# FirstStandaloneMega.net
KiCad netlist of a schematic drawn in EAGLE
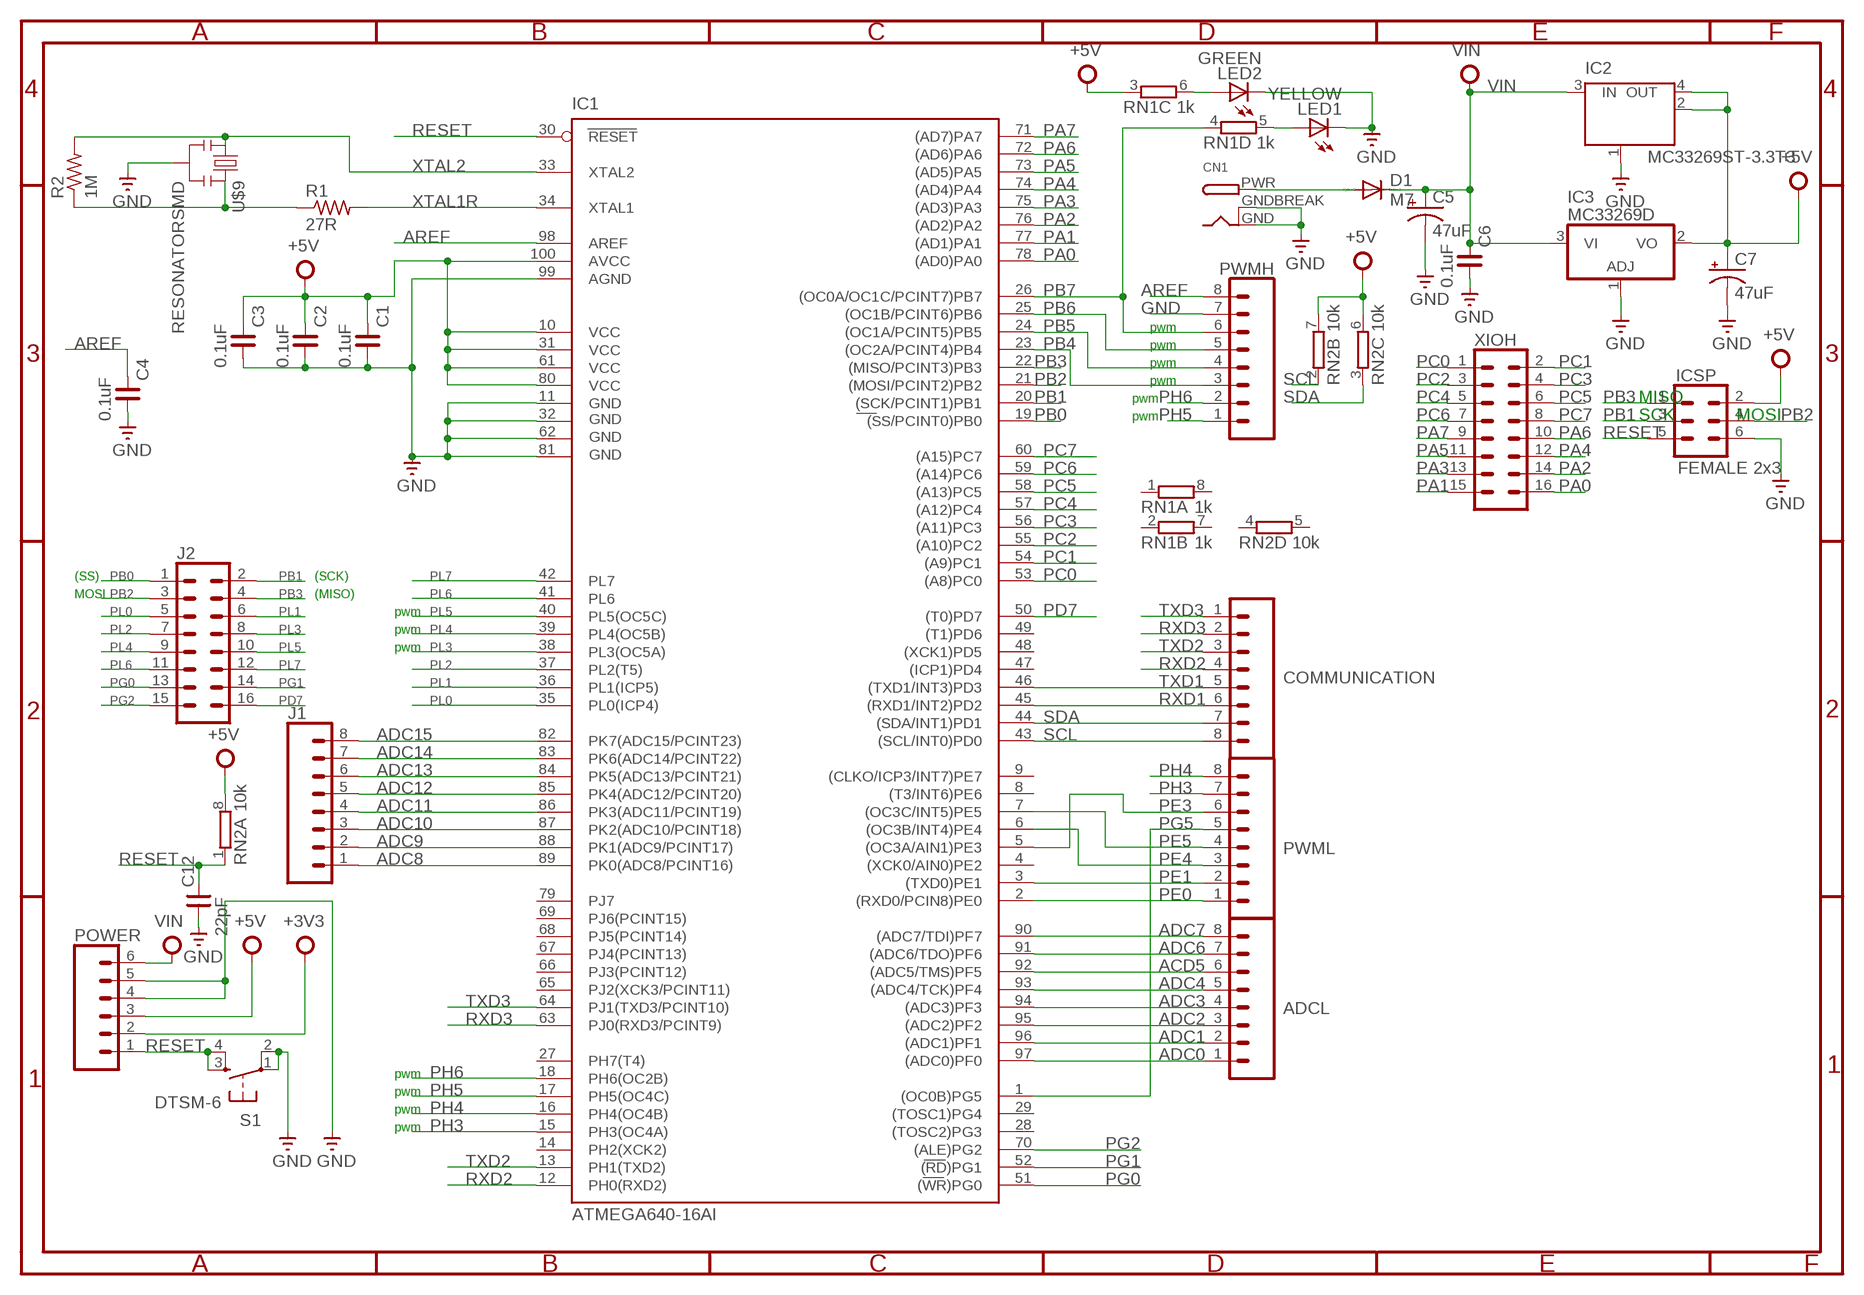
[diagram p0: schematic, sheet 1]

(export (version "E")
  (design (tool "Eeschema 10.0.6"))
  (components
    (comp (ref "ADCL")
      (value "CONN_08\"")
      (footprint "eagle-import:1X08")
      (libsource (lib "eagle-import") (part "CONN_08{dblquote}"))
    )
    (comp (ref "C1")
      (value "0.1uF")
      (footprint "eagle-import:C0805")
      (libsource (lib "eagle-import") (part "C_0805"))
    )
    (comp (ref "C2")
      (value "0.1uF")
      (footprint "eagle-import:C0805")
      (libsource (lib "eagle-import") (part "C_0805"))
    )
    (comp (ref "C3")
      (value "0.1uF")
      (footprint "eagle-import:C0805")
      (libsource (lib "eagle-import") (part "C_0805"))
    )
    (comp (ref "C4")
      (value "0.1uF")
      (footprint "eagle-import:C0805")
      (libsource (lib "eagle-import") (part "C_0805"))
    )
    (comp (ref "C5")
      (value "47uF")
      (footprint "eagle-import:PANASONIC_D")
      (libsource (lib "eagle-import") (part "CPOL-USD"))
    )
    (comp (ref "C6")
      (value "0.1uF")
      (footprint "eagle-import:C0805")
      (libsource (lib "eagle-import") (part "C_0805"))
    )
    (comp (ref "C7")
      (value "47uF")
      (footprint "eagle-import:PANASONIC_D")
      (libsource (lib "eagle-import") (part "CPOL-USD"))
    )
    (comp (ref "C12")
      (value "22pF")
      (footprint "eagle-import:0805")
      (libsource (lib "eagle-import") (part "CNP-0805"))
    )
    (comp (ref "CN1")
      (value "DCBARRELPTH")
      (footprint "eagle-import:DCJACK_2MM_PTH")
      (libsource (lib "eagle-import") (part "DCBARRELPTH"))
    )
    (comp (ref "COMMUNICATION")
      (value "CONN_08\"")
      (footprint "eagle-import:1X08")
      (libsource (lib "eagle-import") (part "CONN_08{dblquote}"))
    )
    (comp (ref "D1")
      (value "M7")
      (footprint "eagle-import:SMB")
      (libsource (lib "eagle-import") (part "DIODE-SMB"))
    )
    (comp (ref "IC1")
      (value "ATMEGA640-16AI")
      (footprint "eagle-import:TQFP100")
      (libsource (lib "eagle-import") (part "ATMEGAAI640-16"))
    )
    (comp (ref "IC2")
      (value "MC33269ST-3.3T3")
      (footprint "eagle-import:SOT223")
      (libsource (lib "eagle-import") (part "MC33269ST-3.3T3"))
    )
    (comp (ref "IC3")
      (value "MC33269D")
      (footprint "eagle-import:DPACK")
      (libsource (lib "eagle-import") (part "MC33269?D"))
    )
    (comp (ref "ICSP")
      (value "FEMALE 2x3")
      (footprint "eagle-import:2X3")
      (libsource (lib "eagle-import") (part "CONN_03X2FEMALE"))
    )
    (comp (ref "J1")
      (value "CONN_08\"")
      (footprint "eagle-import:1X08")
      (libsource (lib "eagle-import") (part "CONN_08{dblquote}"))
    )
    (comp (ref "J2")
      (value "CONN_08X2")
      (footprint "eagle-import:2X8")
      (libsource (lib "eagle-import") (part "CONN_08X2"))
    )
    (comp (ref "LED1")
      (value "YELLOW")
      (footprint "eagle-import:CHIPLED_0805")
      (libsource (lib "eagle-import") (part "LEDCHIPLED_0805"))
    )
    (comp (ref "LED2")
      (value "GREEN")
      (footprint "eagle-import:CHIPLED_0805")
      (libsource (lib "eagle-import") (part "LEDCHIPLED_0805"))
    )
    (comp (ref "POWER")
      (value "CONN_06SILK_FEMALE_PTH")
      (footprint "eagle-import:1X06")
      (libsource (lib "eagle-import") (part "CONN_06SILK_FEMALE_PTH"))
    )
    (comp (ref "PWMH")
      (value "CONN_08\"")
      (footprint "eagle-import:1X08")
      (libsource (lib "eagle-import") (part "CONN_08{dblquote}"))
    )
    (comp (ref "PWML")
      (value "CONN_08\"")
      (footprint "eagle-import:1X08")
      (libsource (lib "eagle-import") (part "CONN_08{dblquote}"))
    )
    (comp (ref "R1")
      (value "27R")
      (footprint "eagle-import:R0805")
      (libsource (lib "eagle-import") (part "R-US_R0805"))
    )
    (comp (ref "R2")
      (value "1M")
      (footprint "eagle-import:R0805")
      (libsource (lib "eagle-import") (part "R-US_R0805"))
    )
    (comp (ref "RN1")
      (value "1k")
      (footprint "eagle-import:CAY16")
      (libsource (lib "eagle-import") (part "4R-NCAY16"))
    )
    (comp (ref "RN2")
      (value "10k")
      (footprint "eagle-import:CAY16")
      (libsource (lib "eagle-import") (part "4R-NCAY16"))
    )
    (comp (ref "S1")
      (value "DTSM-6")
      (footprint "eagle-import:DTSM-6")
      (libsource (lib "eagle-import") (part "DTSM-6"))
    )
    (comp (ref "U$9")
      (value "RESONATORSMD")
      (footprint "eagle-import:RESONATOR-SMD")
      (libsource (lib "eagle-import") (part "RESONATORSMD"))
    )
    (comp (ref "XIOH")
      (value "CONN_08X2")
      (footprint "eagle-import:2X8")
      (libsource (lib "eagle-import") (part "CONN_08X2"))
    )
  )
  (nets
    (net (code "1") (name "+3V3") (class "Default")
      (node (ref "POWER") (pin "2") (pinfunction "2_2") (pintype "passive"))
    )
    (net (code "2") (name "+5V") (class "Default")
      (node (ref "C1") (pin "2") (pinfunction "2_2") (pintype "passive"))
      (node (ref "C2") (pin "2") (pinfunction "2_2") (pintype "passive"))
      (node (ref "C3") (pin "2") (pinfunction "2_2") (pintype "passive"))
      (node (ref "C7") (pin "+") (pinfunction "+_+") (pintype "passive"))
      (node (ref "IC1") (pin "10") (pinfunction "VCC_10") (pintype "power_in"))
      (node (ref "IC1") (pin "100") (pinfunction "AVCC_100") (pintype "power_in"))
      (node (ref "IC1") (pin "31") (pinfunction "VCC1_31") (pintype "power_in"))
      (node (ref "IC1") (pin "61") (pinfunction "VCC2_61") (pintype "power_in"))
      (node (ref "IC1") (pin "80") (pinfunction "VCC3_80") (pintype "power_in"))
      (node (ref "IC2") (pin "2") (pinfunction "OUT_2") (pintype "passive"))
      (node (ref "IC2") (pin "4") (pinfunction "OUT_4") (pintype "passive"))
      (node (ref "IC3") (pin "2") (pinfunction "VO_2") (pintype "passive"))
      (node (ref "ICSP") (pin "2") (pinfunction "2_2") (pintype "bidirectional"))
      (node (ref "POWER") (pin "3") (pinfunction "3_3") (pintype "passive"))
      (node (ref "RN1") (pin "3") (pinfunction "1_3") (pintype "passive"))
      (node (ref "RN2") (pin "6") (pinfunction "2_6") (pintype "passive"))
      (node (ref "RN2") (pin "7") (pinfunction "2_7") (pintype "passive"))
      (node (ref "RN2") (pin "8") (pinfunction "2_8") (pintype "passive"))
    )
    (net (code "3") (name "/ACD5") (class "Default")
      (node (ref "ADCL") (pin "6") (pinfunction "6_6") (pintype "passive"))
      (node (ref "IC1") (pin "92") (pinfunction "(ADC5/TMS)PF5_92") (pintype "bidirectional"))
    )
    (net (code "4") (name "/ADC0") (class "Default")
      (node (ref "ADCL") (pin "1") (pinfunction "1_1") (pintype "passive"))
      (node (ref "IC1") (pin "97") (pinfunction "(ADC0)PF0_97") (pintype "bidirectional"))
    )
    (net (code "5") (name "/ADC1") (class "Default")
      (node (ref "ADCL") (pin "2") (pinfunction "2_2") (pintype "passive"))
      (node (ref "IC1") (pin "96") (pinfunction "(ADC1)PF1_96") (pintype "bidirectional"))
    )
    (net (code "6") (name "/ADC2") (class "Default")
      (node (ref "ADCL") (pin "3") (pinfunction "3_3") (pintype "passive"))
      (node (ref "IC1") (pin "95") (pinfunction "(ADC2)PF2_95") (pintype "bidirectional"))
    )
    (net (code "7") (name "/ADC3") (class "Default")
      (node (ref "ADCL") (pin "4") (pinfunction "4_4") (pintype "passive"))
      (node (ref "IC1") (pin "94") (pinfunction "(ADC3)PF3_94") (pintype "bidirectional"))
    )
    (net (code "8") (name "/ADC4") (class "Default")
      (node (ref "ADCL") (pin "5") (pinfunction "5_5") (pintype "passive"))
      (node (ref "IC1") (pin "93") (pinfunction "(ADC4/TCK)PF4_93") (pintype "bidirectional"))
    )
    (net (code "9") (name "/ADC6") (class "Default")
      (node (ref "ADCL") (pin "7") (pinfunction "7_7") (pintype "passive"))
      (node (ref "IC1") (pin "91") (pinfunction "(ADC6/TDO)PF6_91") (pintype "bidirectional"))
    )
    (net (code "10") (name "/ADC7") (class "Default")
      (node (ref "ADCL") (pin "8") (pinfunction "8_8") (pintype "passive"))
      (node (ref "IC1") (pin "90") (pinfunction "(ADC7/TDI)PF7_90") (pintype "bidirectional"))
    )
    (net (code "11") (name "/ADC8") (class "Default")
      (node (ref "IC1") (pin "89") (pinfunction "PK0(ADC8/PCINT16)_89") (pintype "bidirectional"))
      (node (ref "J1") (pin "1") (pinfunction "1_1") (pintype "passive"))
    )
    (net (code "12") (name "/ADC9") (class "Default")
      (node (ref "IC1") (pin "88") (pinfunction "PK1(ADC9/PCINT17)_88") (pintype "bidirectional"))
      (node (ref "J1") (pin "2") (pinfunction "2_2") (pintype "passive"))
    )
    (net (code "13") (name "/ADC10") (class "Default")
      (node (ref "IC1") (pin "87") (pinfunction "PK2(ADC10/PCINT18)_87") (pintype "bidirectional"))
      (node (ref "J1") (pin "3") (pinfunction "3_3") (pintype "passive"))
    )
    (net (code "14") (name "/ADC11") (class "Default")
      (node (ref "IC1") (pin "86") (pinfunction "PK3(ADC11/PCINT19)_86") (pintype "bidirectional"))
      (node (ref "J1") (pin "4") (pinfunction "4_4") (pintype "passive"))
    )
    (net (code "15") (name "/ADC12") (class "Default")
      (node (ref "IC1") (pin "85") (pinfunction "PK4(ADC12/PCINT20)_85") (pintype "bidirectional"))
      (node (ref "J1") (pin "5") (pinfunction "5_5") (pintype "passive"))
    )
    (net (code "16") (name "/ADC13") (class "Default")
      (node (ref "IC1") (pin "84") (pinfunction "PK5(ADC13/PCINT21)_84") (pintype "bidirectional"))
      (node (ref "J1") (pin "6") (pinfunction "6_6") (pintype "passive"))
    )
    (net (code "17") (name "/ADC14") (class "Default")
      (node (ref "IC1") (pin "83") (pinfunction "PK6(ADC14/PCINT22)_83") (pintype "bidirectional"))
      (node (ref "J1") (pin "7") (pinfunction "7_7") (pintype "passive"))
    )
    (net (code "18") (name "/ADC15") (class "Default")
      (node (ref "IC1") (pin "82") (pinfunction "PK7(ADC15/PCINT23)_82") (pintype "bidirectional"))
      (node (ref "J1") (pin "8") (pinfunction "8_8") (pintype "passive"))
    )
    (net (code "19") (name "/AREF") (class "Default")
      (node (ref "C4") (pin "2") (pinfunction "2_2") (pintype "passive"))
      (node (ref "IC1") (pin "98") (pinfunction "AREF_98") (pintype "bidirectional"))
      (node (ref "PWMH") (pin "8") (pinfunction "8_8") (pintype "passive"))
    )
    (net (code "20") (name "/PA0") (class "Default")
      (node (ref "IC1") (pin "78") (pinfunction "(AD0)PA0_78") (pintype "bidirectional"))
      (node (ref "XIOH") (pin "16") (pinfunction "16_16") (pintype "passive"))
    )
    (net (code "21") (name "/PA1") (class "Default")
      (node (ref "IC1") (pin "77") (pinfunction "(AD1)PA1_77") (pintype "bidirectional"))
      (node (ref "XIOH") (pin "15") (pinfunction "15_15") (pintype "passive"))
    )
    (net (code "22") (name "/PA2") (class "Default")
      (node (ref "IC1") (pin "76") (pinfunction "(AD2)PA2_76") (pintype "bidirectional"))
      (node (ref "XIOH") (pin "14") (pinfunction "14_14") (pintype "passive"))
    )
    (net (code "23") (name "/PA3") (class "Default")
      (node (ref "IC1") (pin "75") (pinfunction "(AD3)PA3_75") (pintype "bidirectional"))
      (node (ref "XIOH") (pin "13") (pinfunction "13_13") (pintype "passive"))
    )
    (net (code "24") (name "/PA4") (class "Default")
      (node (ref "IC1") (pin "74") (pinfunction "(AD4)PA4_74") (pintype "bidirectional"))
      (node (ref "XIOH") (pin "12") (pinfunction "12_12") (pintype "passive"))
    )
    (net (code "25") (name "/PA5") (class "Default")
      (node (ref "IC1") (pin "73") (pinfunction "(AD5)PA5_73") (pintype "bidirectional"))
      (node (ref "XIOH") (pin "11") (pinfunction "11_11") (pintype "passive"))
    )
    (net (code "26") (name "/PA6") (class "Default")
      (node (ref "IC1") (pin "72") (pinfunction "(AD6)PA6_72") (pintype "bidirectional"))
      (node (ref "XIOH") (pin "10") (pinfunction "10_10") (pintype "passive"))
    )
    (net (code "27") (name "/PA7") (class "Default")
      (node (ref "IC1") (pin "71") (pinfunction "(AD7)PA7_71") (pintype "bidirectional"))
      (node (ref "XIOH") (pin "9") (pinfunction "9_9") (pintype "passive"))
    )
    (net (code "28") (name "/PB0") (class "Default")
      (node (ref "IC1") (pin "19") (pinfunction "(SS/PCINT0)PB0_19") (pintype "bidirectional"))
      (node (ref "J2") (pin "1") (pinfunction "1_1") (pintype "passive"))
    )
    (net (code "29") (name "/PB1") (class "Default")
      (node (ref "IC1") (pin "20") (pinfunction "(SCK/PCINT1)PB1_20") (pintype "bidirectional"))
      (node (ref "ICSP") (pin "3") (pinfunction "3_3") (pintype "bidirectional"))
      (node (ref "J2") (pin "2") (pinfunction "2_2") (pintype "passive"))
    )
    (net (code "30") (name "/PB2") (class "Default")
      (node (ref "IC1") (pin "21") (pinfunction "(MOSI/PCINT2)PB2_21") (pintype "bidirectional"))
      (node (ref "ICSP") (pin "4") (pinfunction "4_4") (pintype "bidirectional"))
      (node (ref "J2") (pin "3") (pinfunction "3_3") (pintype "passive"))
    )
    (net (code "31") (name "/PB3") (class "Default")
      (node (ref "IC1") (pin "22") (pinfunction "(MISO/PCINT3)PB3_22") (pintype "bidirectional"))
      (node (ref "ICSP") (pin "1") (pinfunction "1_1") (pintype "bidirectional"))
      (node (ref "J2") (pin "4") (pinfunction "4_4") (pintype "passive"))
    )
    (net (code "32") (name "/PB4") (class "Default")
      (node (ref "IC1") (pin "23") (pinfunction "(OC2A/PCINT4)PB4_23") (pintype "bidirectional"))
      (node (ref "PWMH") (pin "3") (pinfunction "3_3") (pintype "passive"))
    )
    (net (code "33") (name "/PB5") (class "Default")
      (node (ref "IC1") (pin "24") (pinfunction "(OC1A/PCINT5)PB5_24") (pintype "bidirectional"))
      (node (ref "PWMH") (pin "4") (pinfunction "4_4") (pintype "passive"))
    )
    (net (code "34") (name "/PB6") (class "Default")
      (node (ref "IC1") (pin "25") (pinfunction "(OC1B/PCINT6)PB6_25") (pintype "bidirectional"))
      (node (ref "PWMH") (pin "5") (pinfunction "5_5") (pintype "passive"))
    )
    (net (code "35") (name "/PB7") (class "Default")
      (node (ref "IC1") (pin "26") (pinfunction "(OC0A/OC1C/PCINT7)PB7_26") (pintype "bidirectional"))
      (node (ref "PWMH") (pin "6") (pinfunction "6_6") (pintype "passive"))
      (node (ref "RN1") (pin "4") (pinfunction "1_4") (pintype "passive"))
    )
    (net (code "36") (name "/PC0") (class "Default")
      (node (ref "IC1") (pin "53") (pinfunction "(A8)PC0_53") (pintype "bidirectional"))
      (node (ref "XIOH") (pin "1") (pinfunction "1_1") (pintype "passive"))
    )
    (net (code "37") (name "/PC1") (class "Default")
      (node (ref "IC1") (pin "54") (pinfunction "(A9)PC1_54") (pintype "bidirectional"))
      (node (ref "XIOH") (pin "2") (pinfunction "2_2") (pintype "passive"))
    )
    (net (code "38") (name "/PC2") (class "Default")
      (node (ref "IC1") (pin "55") (pinfunction "(A10)PC2_55") (pintype "bidirectional"))
      (node (ref "XIOH") (pin "3") (pinfunction "3_3") (pintype "passive"))
    )
    (net (code "39") (name "/PC3") (class "Default")
      (node (ref "IC1") (pin "56") (pinfunction "(A11)PC3_56") (pintype "bidirectional"))
      (node (ref "XIOH") (pin "4") (pinfunction "4_4") (pintype "passive"))
    )
    (net (code "40") (name "/PC4") (class "Default")
      (node (ref "IC1") (pin "57") (pinfunction "(A12)PC4_57") (pintype "bidirectional"))
      (node (ref "XIOH") (pin "5") (pinfunction "5_5") (pintype "passive"))
    )
    (net (code "41") (name "/PC5") (class "Default")
      (node (ref "IC1") (pin "58") (pinfunction "(A13)PC5_58") (pintype "bidirectional"))
      (node (ref "XIOH") (pin "6") (pinfunction "6_6") (pintype "passive"))
    )
    (net (code "42") (name "/PC6") (class "Default")
      (node (ref "IC1") (pin "59") (pinfunction "(A14)PC6_59") (pintype "bidirectional"))
      (node (ref "XIOH") (pin "7") (pinfunction "7_7") (pintype "passive"))
    )
    (net (code "43") (name "/PC7") (class "Default")
      (node (ref "IC1") (pin "60") (pinfunction "(A15)PC7_60") (pintype "bidirectional"))
      (node (ref "XIOH") (pin "8") (pinfunction "8_8") (pintype "passive"))
    )
    (net (code "44") (name "/PD7") (class "Default")
      (node (ref "IC1") (pin "50") (pinfunction "(T0)PD7_50") (pintype "bidirectional"))
      (node (ref "J2") (pin "16") (pinfunction "16_16") (pintype "passive"))
    )
    (net (code "45") (name "/PE0") (class "Default")
      (node (ref "IC1") (pin "2") (pinfunction "(RXD0/PCIN8)PE0_2") (pintype "bidirectional"))
      (node (ref "PWML") (pin "1") (pinfunction "1_1") (pintype "passive"))
    )
    (net (code "46") (name "/PE1") (class "Default")
      (node (ref "IC1") (pin "3") (pinfunction "(TXD0)PE1_3") (pintype "bidirectional"))
      (node (ref "PWML") (pin "2") (pinfunction "2_2") (pintype "passive"))
    )
    (net (code "47") (name "/PE3") (class "Default")
      (node (ref "IC1") (pin "5") (pinfunction "(OC3A/AIN1)PE3_5") (pintype "bidirectional"))
      (node (ref "PWML") (pin "6") (pinfunction "6_6") (pintype "passive"))
    )
    (net (code "48") (name "/PE4") (class "Default")
      (node (ref "IC1") (pin "6") (pinfunction "(OC3B/INT4)PE4_6") (pintype "bidirectional"))
      (node (ref "PWML") (pin "3") (pinfunction "3_3") (pintype "passive"))
    )
    (net (code "49") (name "/PE5") (class "Default")
      (node (ref "IC1") (pin "7") (pinfunction "(OC3C/INT5)PE5_7") (pintype "bidirectional"))
      (node (ref "PWML") (pin "4") (pinfunction "4_4") (pintype "passive"))
    )
    (net (code "50") (name "/PG0") (class "Default")
      (node (ref "IC1") (pin "51") (pinfunction "(WR)PG0_51") (pintype "bidirectional"))
      (node (ref "J2") (pin "13") (pinfunction "13_13") (pintype "passive"))
    )
    (net (code "51") (name "/PG1") (class "Default")
      (node (ref "IC1") (pin "52") (pinfunction "(RD)PG1_52") (pintype "bidirectional"))
      (node (ref "J2") (pin "14") (pinfunction "14_14") (pintype "passive"))
    )
    (net (code "52") (name "/PG2") (class "Default")
      (node (ref "IC1") (pin "70") (pinfunction "(ALE)PG2_70") (pintype "bidirectional"))
      (node (ref "J2") (pin "15") (pinfunction "15_15") (pintype "passive"))
    )
    (net (code "53") (name "/PG5") (class "Default")
      (node (ref "IC1") (pin "1") (pinfunction "(OC0B)PG5_1") (pintype "bidirectional"))
      (node (ref "PWML") (pin "5") (pinfunction "5_5") (pintype "passive"))
    )
    (net (code "54") (name "/PH3") (class "Default")
      (node (ref "IC1") (pin "15") (pinfunction "PH3(OC4A)_15") (pintype "bidirectional"))
      (node (ref "PWML") (pin "7") (pinfunction "7_7") (pintype "passive"))
    )
    (net (code "55") (name "/PH4") (class "Default")
      (node (ref "IC1") (pin "16") (pinfunction "PH4(OC4B)_16") (pintype "bidirectional"))
      (node (ref "PWML") (pin "8") (pinfunction "8_8") (pintype "passive"))
    )
    (net (code "56") (name "/PH5") (class "Default")
      (node (ref "IC1") (pin "17") (pinfunction "PH5(OC4C)_17") (pintype "bidirectional"))
      (node (ref "PWMH") (pin "1") (pinfunction "1_1") (pintype "passive"))
    )
    (net (code "57") (name "/PH6") (class "Default")
      (node (ref "IC1") (pin "18") (pinfunction "PH6(OC2B)_18") (pintype "bidirectional"))
      (node (ref "PWMH") (pin "2") (pinfunction "2_2") (pintype "passive"))
    )
    (net (code "58") (name "/PL0") (class "Default")
      (node (ref "IC1") (pin "35") (pinfunction "PL0(ICP4)_35") (pintype "bidirectional"))
      (node (ref "J2") (pin "5") (pinfunction "5_5") (pintype "passive"))
    )
    (net (code "59") (name "/PL1") (class "Default")
      (node (ref "IC1") (pin "36") (pinfunction "PL1(ICP5)_36") (pintype "bidirectional"))
      (node (ref "J2") (pin "6") (pinfunction "6_6") (pintype "passive"))
    )
    (net (code "60") (name "/PL2") (class "Default")
      (node (ref "IC1") (pin "37") (pinfunction "PL2(T5)_37") (pintype "bidirectional"))
      (node (ref "J2") (pin "7") (pinfunction "7_7") (pintype "passive"))
    )
    (net (code "61") (name "/PL3") (class "Default")
      (node (ref "IC1") (pin "38") (pinfunction "PL3(OC5A)_38") (pintype "bidirectional"))
      (node (ref "J2") (pin "8") (pinfunction "8_8") (pintype "passive"))
    )
    (net (code "62") (name "/PL4") (class "Default")
      (node (ref "IC1") (pin "39") (pinfunction "PL4(OC5B)_39") (pintype "bidirectional"))
      (node (ref "J2") (pin "9") (pinfunction "9_9") (pintype "passive"))
    )
    (net (code "63") (name "/PL5") (class "Default")
      (node (ref "IC1") (pin "40") (pinfunction "PL5(OC5C)_40") (pintype "bidirectional"))
      (node (ref "J2") (pin "10") (pinfunction "10_10") (pintype "passive"))
    )
    (net (code "64") (name "/PL6") (class "Default")
      (node (ref "IC1") (pin "41") (pinfunction "PL6_41") (pintype "bidirectional"))
      (node (ref "J2") (pin "11") (pinfunction "11_11") (pintype "passive"))
    )
    (net (code "65") (name "/PL7") (class "Default")
      (node (ref "IC1") (pin "42") (pinfunction "PL7_42") (pintype "bidirectional"))
      (node (ref "J2") (pin "12") (pinfunction "12_12") (pintype "passive"))
    )
    (net (code "66") (name "/RESET") (class "Default")
      (node (ref "C12") (pin "2") (pinfunction "2_2") (pintype "passive"))
      (node (ref "IC1") (pin "30") (pinfunction "RESET_30") (pintype "input"))
      (node (ref "ICSP") (pin "5") (pinfunction "5_5") (pintype "bidirectional"))
      (node (ref "POWER") (pin "1") (pinfunction "1_1") (pintype "passive"))
      (node (ref "RN2") (pin "1") (pinfunction "1_1") (pintype "passive"))
      (node (ref "S1") (pin "3") (pinfunction "3_3") (pintype "passive"))
      (node (ref "S1") (pin "4") (pinfunction "4_4") (pintype "passive"))
    )
    (net (code "67") (name "/RXD1") (class "Default")
      (node (ref "COMMUNICATION") (pin "6") (pinfunction "6_6") (pintype "passive"))
      (node (ref "IC1") (pin "45") (pinfunction "(RXD1/INT2)PD2_45") (pintype "bidirectional"))
    )
    (net (code "68") (name "/RXD2") (class "Default")
      (node (ref "COMMUNICATION") (pin "4") (pinfunction "4_4") (pintype "passive"))
      (node (ref "IC1") (pin "12") (pinfunction "PH0(RXD2)_12") (pintype "bidirectional"))
    )
    (net (code "69") (name "/RXD3") (class "Default")
      (node (ref "COMMUNICATION") (pin "2") (pinfunction "2_2") (pintype "passive"))
      (node (ref "IC1") (pin "63") (pinfunction "PJ0(RXD3/PCINT9)_63") (pintype "bidirectional"))
    )
    (net (code "70") (name "/SCL") (class "Default")
      (node (ref "COMMUNICATION") (pin "8") (pinfunction "8_8") (pintype "passive"))
      (node (ref "IC1") (pin "43") (pinfunction "(SCL/INT0)PD0_43") (pintype "bidirectional"))
      (node (ref "RN2") (pin "2") (pinfunction "1_2") (pintype "passive"))
    )
    (net (code "71") (name "/SDA") (class "Default")
      (node (ref "COMMUNICATION") (pin "7") (pinfunction "7_7") (pintype "passive"))
      (node (ref "IC1") (pin "44") (pinfunction "(SDA/INT1)PD1_44") (pintype "bidirectional"))
      (node (ref "RN2") (pin "3") (pinfunction "1_3") (pintype "passive"))
    )
    (net (code "72") (name "/TXD1") (class "Default")
      (node (ref "COMMUNICATION") (pin "5") (pinfunction "5_5") (pintype "passive"))
      (node (ref "IC1") (pin "46") (pinfunction "(TXD1/INT3)PD3_46") (pintype "bidirectional"))
    )
    (net (code "73") (name "/TXD2") (class "Default")
      (node (ref "COMMUNICATION") (pin "3") (pinfunction "3_3") (pintype "passive"))
      (node (ref "IC1") (pin "13") (pinfunction "PH1(TXD2)_13") (pintype "bidirectional"))
    )
    (net (code "74") (name "/TXD3") (class "Default")
      (node (ref "COMMUNICATION") (pin "1") (pinfunction "1_1") (pintype "passive"))
      (node (ref "IC1") (pin "64") (pinfunction "PJ1(TXD3/PCINT10)_64") (pintype "bidirectional"))
    )
    (net (code "75") (name "/XTAL1R") (class "Default")
      (node (ref "IC1") (pin "34") (pinfunction "XTAL1_34") (pintype "input"))
      (node (ref "R1") (pin "2") (pinfunction "2_2") (pintype "passive"))
    )
    (net (code "76") (name "/XTAL2") (class "Default")
      (node (ref "IC1") (pin "33") (pinfunction "XTAL2_33") (pintype "output"))
      (node (ref "R2") (pin "2") (pinfunction "2_2") (pintype "passive"))
      (node (ref "U$9") (pin "1") (pinfunction "1_1") (pintype "passive"))
    )
    (net (code "77") (name "GND") (class "Default")
      (node (ref "C1") (pin "1") (pinfunction "1_1") (pintype "passive"))
      (node (ref "C12") (pin "1") (pinfunction "1_1") (pintype "passive"))
      (node (ref "C2") (pin "1") (pinfunction "1_1") (pintype "passive"))
      (node (ref "C3") (pin "1") (pinfunction "1_1") (pintype "passive"))
      (node (ref "C4") (pin "1") (pinfunction "1_1") (pintype "passive"))
      (node (ref "C5") (pin "-") (pinfunction "-_-") (pintype "passive"))
      (node (ref "C6") (pin "1") (pinfunction "1_1") (pintype "passive"))
      (node (ref "C7") (pin "-") (pinfunction "-_-") (pintype "passive"))
      (node (ref "CN1") (pin "GND") (pinfunction "GND_GND") (pintype "power_in"))
      (node (ref "CN1") (pin "GNDBREAK") (pinfunction "GNDBREAK_GNDBREAK") (pintype "power_in"))
      (node (ref "IC1") (pin "11") (pinfunction "GND_11") (pintype "power_in"))
      (node (ref "IC1") (pin "32") (pinfunction "GND1_32") (pintype "power_in"))
      (node (ref "IC1") (pin "62") (pinfunction "GND2_62") (pintype "power_in"))
      (node (ref "IC1") (pin "81") (pinfunction "GND3_81") (pintype "power_in"))
      (node (ref "IC1") (pin "99") (pinfunction "AGND_99") (pintype "power_in"))
      (node (ref "IC2") (pin "1") (pinfunction "GND/ADJ_1") (pintype "input"))
      (node (ref "IC3") (pin "1") (pinfunction "ADJ_1") (pintype "input"))
      (node (ref "ICSP") (pin "6") (pinfunction "6_6") (pintype "bidirectional"))
      (node (ref "LED1") (pin "C") (pinfunction "C_C") (pintype "passive"))
      (node (ref "LED2") (pin "C") (pinfunction "C_C") (pintype "passive"))
      (node (ref "POWER") (pin "4") (pinfunction "4_4") (pintype "passive"))
      (node (ref "POWER") (pin "5") (pinfunction "5_5") (pintype "passive"))
      (node (ref "PWMH") (pin "7") (pinfunction "7_7") (pintype "passive"))
      (node (ref "S1") (pin "1") (pinfunction "1_1") (pintype "passive"))
      (node (ref "S1") (pin "2") (pinfunction "2_2") (pintype "passive"))
      (node (ref "U$9") (pin "2") (pinfunction "2_2") (pintype "passive"))
    )
    (net (code "78") (name "Net-(CN1-PadPWR)") (class "Default")
      (node (ref "CN1") (pin "PWR") (pinfunction "PWR_PWR") (pintype "power_in"))
      (node (ref "D1") (pin "A") (pinfunction "A_A") (pintype "passive"))
    )
    (net (code "79") (name "Net-(R1-Pad1)") (class "Default")
      (node (ref "R1") (pin "1") (pinfunction "1_1") (pintype "passive"))
      (node (ref "R2") (pin "1") (pinfunction "1_1") (pintype "passive"))
      (node (ref "U$9") (pin "3") (pinfunction "3_3") (pintype "passive"))
    )
    (net (code "80") (name "Net-(RN1C-2)") (class "Default")
      (node (ref "LED2") (pin "A") (pinfunction "A_A") (pintype "passive"))
      (node (ref "RN1") (pin "6") (pinfunction "2_6") (pintype "passive"))
    )
    (net (code "81") (name "Net-(RN1D-2)") (class "Default")
      (node (ref "LED1") (pin "A") (pinfunction "A_A") (pintype "passive"))
      (node (ref "RN1") (pin "5") (pinfunction "2_5") (pintype "passive"))
    )
    (net (code "82") (name "VIN") (class "Default")
      (node (ref "C5") (pin "+") (pinfunction "+_+") (pintype "passive"))
      (node (ref "C6") (pin "2") (pinfunction "2_2") (pintype "passive"))
      (node (ref "D1") (pin "C") (pinfunction "C_C") (pintype "passive"))
      (node (ref "IC2") (pin "3") (pinfunction "IN_3") (pintype "input"))
      (node (ref "IC3") (pin "3") (pinfunction "VI_3") (pintype "input"))
      (node (ref "POWER") (pin "6") (pinfunction "6_6") (pintype "passive"))
    )
    (net (code "83") (name "unconnected-(IC1-(CLKO{slash}ICP3{slash}INT7)PE7-Pad9)") (class "Default")
      (node (ref "IC1") (pin "9") (pinfunction "(CLKO/ICP3/INT7)PE7_9") (pintype "bidirectional"))
    )
    (net (code "84") (name "unconnected-(IC1-(ICP1)PD4-Pad47)") (class "Default")
      (node (ref "IC1") (pin "47") (pinfunction "(ICP1)PD4_47") (pintype "bidirectional"))
    )
    (net (code "85") (name "unconnected-(IC1-(T1)PD6-Pad49)") (class "Default")
      (node (ref "IC1") (pin "49") (pinfunction "(T1)PD6_49") (pintype "bidirectional"))
    )
    (net (code "86") (name "unconnected-(IC1-(T3{slash}INT6)PE6-Pad8)") (class "Default")
      (node (ref "IC1") (pin "8") (pinfunction "(T3/INT6)PE6_8") (pintype "bidirectional"))
    )
    (net (code "87") (name "unconnected-(IC1-(TOSC1)PG4-Pad29)") (class "Default")
      (node (ref "IC1") (pin "29") (pinfunction "(TOSC1)PG4_29") (pintype "bidirectional"))
    )
    (net (code "88") (name "unconnected-(IC1-(TOSC2)PG3-Pad28)") (class "Default")
      (node (ref "IC1") (pin "28") (pinfunction "(TOSC2)PG3_28") (pintype "bidirectional"))
    )
    (net (code "89") (name "unconnected-(IC1-(XCK0{slash}AIN0)PE2-Pad4)") (class "Default")
      (node (ref "IC1") (pin "4") (pinfunction "(XCK0/AIN0)PE2_4") (pintype "bidirectional"))
    )
    (net (code "90") (name "unconnected-(IC1-(XCK1)PD5-Pad48)") (class "Default")
      (node (ref "IC1") (pin "48") (pinfunction "(XCK1)PD5_48") (pintype "bidirectional"))
    )
    (net (code "91") (name "unconnected-(IC1-PH2(XCK2)-Pad14)") (class "Default")
      (node (ref "IC1") (pin "14") (pinfunction "PH2(XCK2)_14") (pintype "bidirectional"))
    )
    (net (code "92") (name "unconnected-(IC1-PH7(T4)-Pad27)") (class "Default")
      (node (ref "IC1") (pin "27") (pinfunction "PH7(T4)_27") (pintype "bidirectional"))
    )
    (net (code "93") (name "unconnected-(IC1-PJ2(XCK3{slash}PCINT11)-Pad65)") (class "Default")
      (node (ref "IC1") (pin "65") (pinfunction "PJ2(XCK3/PCINT11)_65") (pintype "bidirectional"))
    )
    (net (code "94") (name "unconnected-(IC1-PJ3(PCINT12)-Pad66)") (class "Default")
      (node (ref "IC1") (pin "66") (pinfunction "PJ3(PCINT12)_66") (pintype "bidirectional"))
    )
    (net (code "95") (name "unconnected-(IC1-PJ4(PCINT13)-Pad67)") (class "Default")
      (node (ref "IC1") (pin "67") (pinfunction "PJ4(PCINT13)_67") (pintype "bidirectional"))
    )
    (net (code "96") (name "unconnected-(IC1-PJ5(PCINT14)-Pad68)") (class "Default")
      (node (ref "IC1") (pin "68") (pinfunction "PJ5(PCINT14)_68") (pintype "bidirectional"))
    )
    (net (code "97") (name "unconnected-(IC1-PJ6(PCINT15)-Pad69)") (class "Default")
      (node (ref "IC1") (pin "69") (pinfunction "PJ6(PCINT15)_69") (pintype "bidirectional"))
    )
    (net (code "98") (name "unconnected-(IC1-PJ7-Pad79)") (class "Default")
      (node (ref "IC1") (pin "79") (pinfunction "PJ7_79") (pintype "bidirectional"))
    )
    (net (code "99") (name "unconnected-(RN1-Pad1)") (class "Default")
      (node (ref "RN1") (pin "1") (pinfunction "1_1") (pintype "passive"))
    )
    (net (code "100") (name "unconnected-(RN1A-2-Pad8)") (class "Default")
      (node (ref "RN1") (pin "8") (pinfunction "2_8") (pintype "passive"))
    )
    (net (code "101") (name "unconnected-(RN1B-1-Pad2)") (class "Default")
      (node (ref "RN1") (pin "2") (pinfunction "1_2") (pintype "passive"))
    )
    (net (code "102") (name "unconnected-(RN1B-2-Pad7)") (class "Default")
      (node (ref "RN1") (pin "7") (pinfunction "2_7") (pintype "passive"))
    )
    (net (code "103") (name "unconnected-(RN2D-1-Pad4)") (class "Default")
      (node (ref "RN2") (pin "4") (pinfunction "1_4") (pintype "passive"))
    )
    (net (code "104") (name "unconnected-(RN2D-2-Pad5)") (class "Default")
      (node (ref "RN2") (pin "5") (pinfunction "2_5") (pintype "passive"))
    )
  )
)
